# PWR_IN.net
KiCad netlist of a schematic drawn in Altium Designer
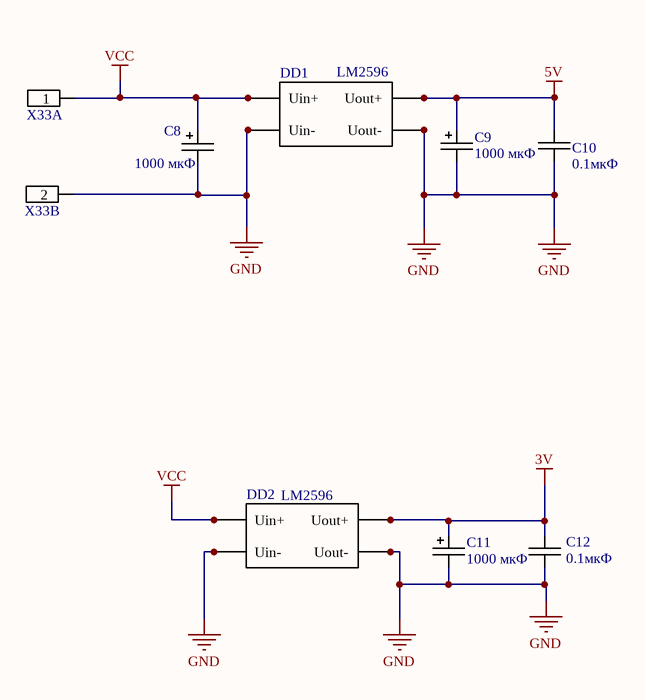
[diagram p0: PWR_IN.SchDoc]

(export (version "E")
  (design (tool "Eeschema 10.0.6"))
  (components
    (comp (ref "C8")
      (value "1000 мкФ")
      (footprint "C_10x5")
      (description "К50-35")
      (fields (field (name "TOLERANCE") "20%"))
      (libsource (lib "Res_end_Cap") (part "Конденсатор 25х12.5"))
    )
    (comp (ref "C9")
      (value "1000 мкФ")
      (footprint "C_10x5")
      (description "К50-35")
      (fields (field (name "TOLERANCE") "20%"))
      (libsource (lib "Res_end_Cap") (part "Конденсатор 25х12.5"))
    )
    (comp (ref "C10")
      (value "0.1мкФ")
      (footprint "C_1206")
      (description "SMD")
      (fields (field (name "VOLTAGE") "50B") (field (name "TOLERANCE") "10%"))
      (libsource (lib "Res_end_Cap") (part "Конденсатор 1210"))
    )
    (comp (ref "C11")
      (value "1000 мкФ")
      (footprint "C_10x5")
      (description "К50-35")
      (fields (field (name "TOLERANCE") "20%"))
      (libsource (lib "Res_end_Cap") (part "Конденсатор 25х12.5"))
    )
    (comp (ref "C12")
      (value "0.1мкФ")
      (footprint "C_1206")
      (description "SMD")
      (fields (field (name "VOLTAGE") "50B") (field (name "TOLERANCE") "10%"))
      (libsource (lib "Res_end_Cap") (part "Конденсатор 1210"))
    )
    (comp (ref "DD1")
      (value "LM2596")
      (footprint "LM2596")
      (description "Блок питания")
      (libsource (lib "MODULE") (part "LM2596"))
    )
    (comp (ref "DD2")
      (value "LM2596")
      (footprint "LM2596")
      (description "Блок питания")
      (libsource (lib "MODULE") (part "LM2596"))
    )
    (comp (ref "X33")
      (value "DG508V-02")
      (footprint "DG508V-02")
      (description "клеммник винтовой 2к.,5.08мм")
      (libsource (lib "Klemniki") (part "DG508V-02"))
    )
  )
  (nets
    (net (code "1") (name "3V") (class "Default")
      (node (ref "C11") (pin "1") (pinfunction "1_1") (pintype "passive"))
      (node (ref "C12") (pin "1") (pinfunction "1_1") (pintype "passive"))
      (node (ref "DD2") (pin "5") (pinfunction "Uout+_5") (pintype "power_in"))
      (node (ref "DD2") (pin "6") (pinfunction "Uout+_6") (pintype "power_in"))
    )
    (net (code "2") (name "5V") (class "Default")
      (node (ref "C10") (pin "1") (pinfunction "1_1") (pintype "passive"))
      (node (ref "C9") (pin "1") (pinfunction "1_1") (pintype "passive"))
      (node (ref "DD1") (pin "5") (pinfunction "Uout+_5") (pintype "power_in"))
      (node (ref "DD1") (pin "6") (pinfunction "Uout+_6") (pintype "power_in"))
    )
    (net (code "3") (name "GND") (class "Default")
      (node (ref "C10") (pin "2") (pinfunction "2_2") (pintype "passive"))
      (node (ref "C11") (pin "2") (pinfunction "2_2") (pintype "passive"))
      (node (ref "C12") (pin "2") (pinfunction "2_2") (pintype "passive"))
      (node (ref "C8") (pin "2") (pinfunction "2_2") (pintype "passive"))
      (node (ref "C9") (pin "2") (pinfunction "2_2") (pintype "passive"))
      (node (ref "DD1") (pin "3") (pinfunction "Uin-_3") (pintype "power_in"))
      (node (ref "DD1") (pin "4") (pinfunction "Uin-_4") (pintype "power_in"))
      (node (ref "DD1") (pin "7") (pinfunction "Uout-_7") (pintype "power_in"))
      (node (ref "DD1") (pin "8") (pinfunction "Uout-_8") (pintype "power_in"))
      (node (ref "DD2") (pin "3") (pinfunction "Uin-_3") (pintype "power_in"))
      (node (ref "DD2") (pin "4") (pinfunction "Uin-_4") (pintype "power_in"))
      (node (ref "DD2") (pin "7") (pinfunction "Uout-_7") (pintype "power_in"))
      (node (ref "DD2") (pin "8") (pinfunction "Uout-_8") (pintype "power_in"))
      (node (ref "X33") (pin "2") (pinfunction "2_2") (pintype "passive"))
    )
    (net (code "4") (name "VCC") (class "Default")
      (node (ref "C8") (pin "1") (pinfunction "1_1") (pintype "passive"))
      (node (ref "DD1") (pin "1") (pinfunction "Uin+_1") (pintype "power_in"))
      (node (ref "DD1") (pin "2") (pinfunction "Uin+_2") (pintype "power_in"))
      (node (ref "DD2") (pin "1") (pinfunction "Uin+_1") (pintype "power_in"))
      (node (ref "DD2") (pin "2") (pinfunction "Uin+_2") (pintype "power_in"))
      (node (ref "X33") (pin "1") (pinfunction "1_1") (pintype "passive"))
    )
  )
)
